# LM2903_CAT5171TBI.net
KiCad netlist of a schematic drawn in Altium Designer
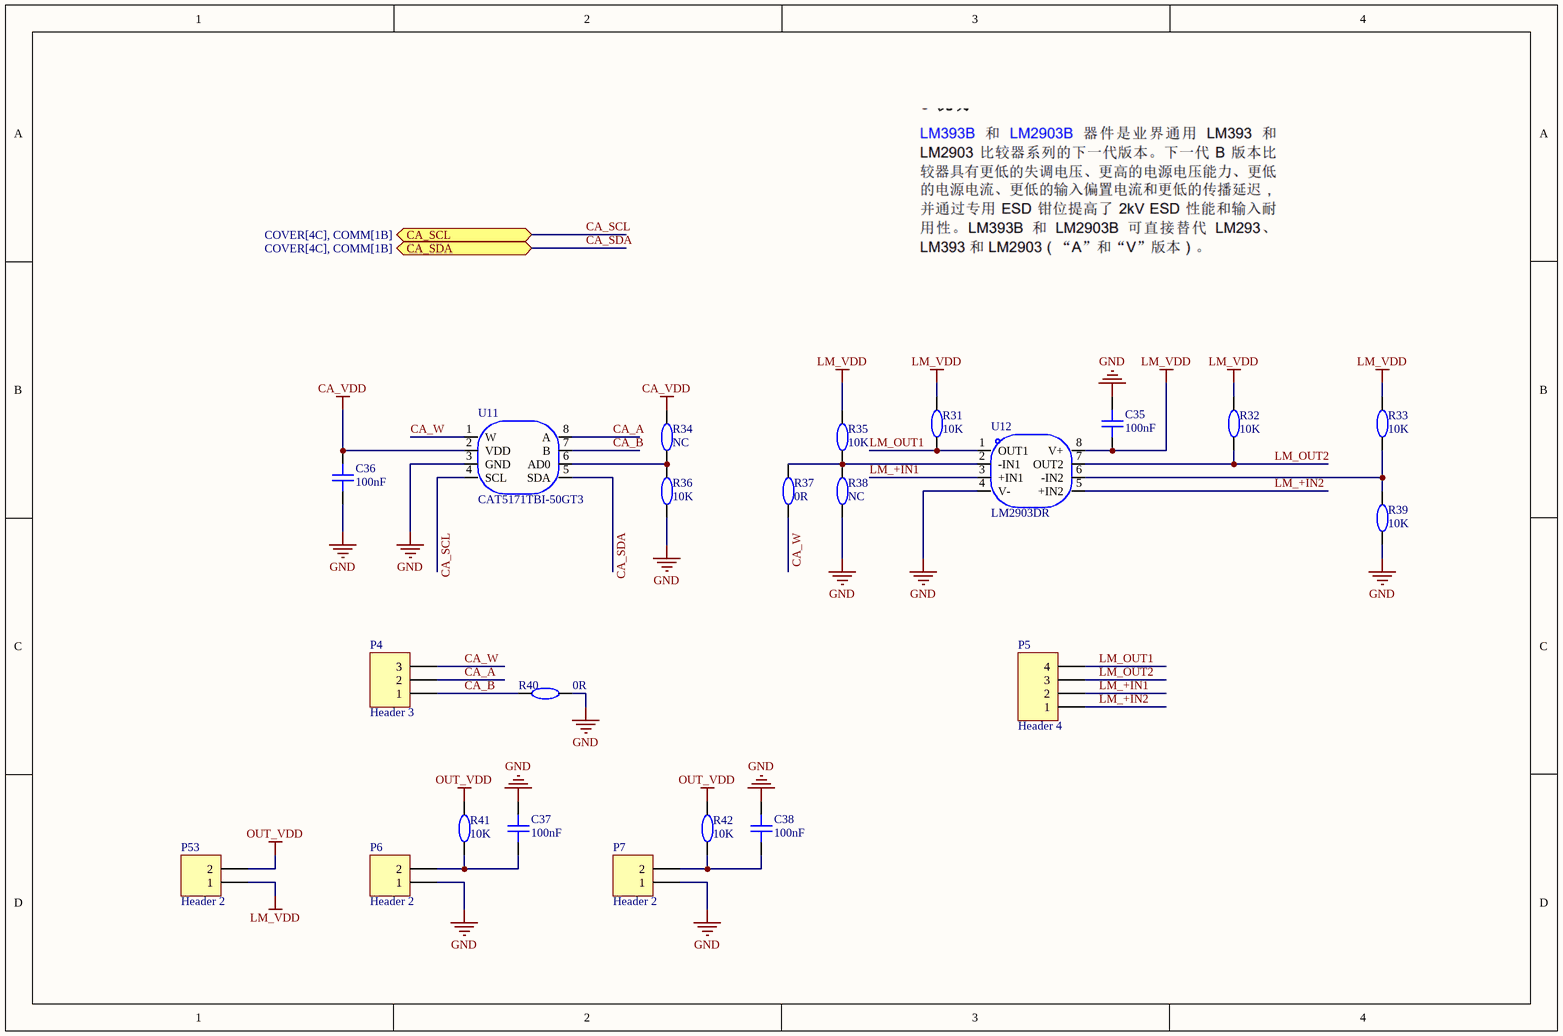
[diagram p0: LM2903+CAT5171TBI.SchDoc]

(export (version "E")
  (design (tool "Eeschema 10.0.6"))
  (components
    (comp (ref "C35")
      (value "100nF")
      (footprint "C0402")
      (fields (field (name "NAME") "100nF"))
      (libsource (lib "my_library") (part "CAP_0402"))
    )
    (comp (ref "C36")
      (value "100nF")
      (footprint "C0402")
      (fields (field (name "NAME") "100nF"))
      (libsource (lib "my_library") (part "CAP_0402"))
    )
    (comp (ref "C37")
      (value "100nF")
      (footprint "C0402")
      (fields (field (name "NAME") "100nF"))
      (libsource (lib "my_library") (part "CAP_0402"))
    )
    (comp (ref "C38")
      (value "100nF")
      (footprint "C0402")
      (fields (field (name "NAME") "100nF"))
      (libsource (lib "my_library") (part "CAP_0402"))
    )
    (comp (ref "P4")
      (value "Header 3")
      (footprint "HDR1X3")
      (description "Header, 3-Pin")
      (fields (field (name "PUBLISHER") "Altium Limited"))
      (libsource (lib "Miscellaneous Connectors") (part "Header 3"))
    )
    (comp (ref "P5")
      (value "Header 4")
      (footprint "HDR1X4")
      (description "Header, 4-Pin")
      (fields (field (name "PUBLISHER") "Altium Limited"))
      (libsource (lib "Miscellaneous Connectors") (part "Header 4"))
    )
    (comp (ref "P6")
      (value "Header 2")
      (footprint "HDR1X2")
      (description "Header, 2-Pin")
      (fields (field (name "PUBLISHER") "Altium Limited"))
      (libsource (lib "Miscellaneous Connectors") (part "Header 2"))
    )
    (comp (ref "P7")
      (value "Header 2")
      (footprint "HDR1X2")
      (description "Header, 2-Pin")
      (fields (field (name "PUBLISHER") "Altium Limited"))
      (libsource (lib "Miscellaneous Connectors") (part "Header 2"))
    )
    (comp (ref "P53")
      (value "Header 2")
      (footprint "HDR1X2")
      (description "Header, 2-Pin")
      (fields (field (name "PUBLISHER") "Altium Limited"))
      (libsource (lib "Miscellaneous Connectors") (part "Header 2"))
    )
    (comp (ref "R31")
      (value "10K")
      (footprint "R0402")
      (fields (field (name "NAME") "10K"))
      (libsource (lib "my_library") (part "Res_0402"))
    )
    (comp (ref "R32")
      (value "10K")
      (footprint "R0402")
      (fields (field (name "NAME") "10K"))
      (libsource (lib "my_library") (part "Res_0402"))
    )
    (comp (ref "R33")
      (value "10K")
      (footprint "R0603")
      (fields (field (name "NAME") "10K"))
      (libsource (lib "my_library") (part "Res_0603"))
    )
    (comp (ref "R34")
      (value "NC")
      (footprint "R0402")
      (fields (field (name "NAME") "NC"))
      (libsource (lib "my_library") (part "Res_0402"))
    )
    (comp (ref "R35")
      (value "10K")
      (footprint "R0603")
      (fields (field (name "NAME") "10K"))
      (libsource (lib "my_library") (part "Res_0603"))
    )
    (comp (ref "R36")
      (value "10K")
      (footprint "R0402")
      (fields (field (name "NAME") "10K"))
      (libsource (lib "my_library") (part "Res_0402"))
    )
    (comp (ref "R37")
      (value "0R")
      (footprint "R0603")
      (fields (field (name "NAME") "0R"))
      (libsource (lib "my_library") (part "Res_0603"))
    )
    (comp (ref "R38")
      (value "NC")
      (footprint "R0603")
      (fields (field (name "NAME") "NC"))
      (libsource (lib "my_library") (part "Res_0603"))
    )
    (comp (ref "R39")
      (value "10K")
      (footprint "R0603")
      (fields (field (name "NAME") "10K"))
      (libsource (lib "my_library") (part "Res_0603"))
    )
    (comp (ref "R40")
      (value "0R")
      (footprint "R0603")
      (fields (field (name "NAME") "0R"))
      (libsource (lib "my_library") (part "Res_0603"))
    )
    (comp (ref "R41")
      (value "10K")
      (footprint "R0402")
      (fields (field (name "NAME") "10K"))
      (libsource (lib "my_library") (part "Res_0402"))
    )
    (comp (ref "R42")
      (value "10K")
      (footprint "R0402")
      (fields (field (name "NAME") "10K"))
      (libsource (lib "my_library") (part "Res_0402"))
    )
    (comp (ref "U11")
      (value "CAT5171TBI-50GT3")
      (footprint "SOT-23-8_L3.0-W1.7-P0.65-LS2.8-BR")
      (fields
        (field (name "MANUFACTURER") "onsemi(安森美)")
        (field (name "TOLERANCE") "±20%")
        (field (name "NAME") "CAT5171TBI-50GT3")
      )
      (libsource (lib "my_library") (part "CAT5171TBI-50GT3"))
    )
    (comp (ref "U12")
      (value "LM2903DR")
      (footprint "SOIC-8_L5.0-W4.0-P1.27-LS6.0-BL")
      (fields (field (name "MANUFACTURER") "TI(德州仪器)") (field (name "NAME") "LM2903DR"))
      (libsource (lib "PCB_Project") (part "LM2903DR"))
    )
  )
  (nets
    (net (code "1") (name "/CA_A") (class "Default")
      (node (ref "P4") (pin "2") (pinfunction "2_2") (pintype "passive"))
      (node (ref "U11") (pin "8") (pinfunction "A_8") (pintype "passive"))
    )
    (net (code "2") (name "/CA_B") (class "Default")
      (node (ref "P4") (pin "1") (pinfunction "1_1") (pintype "passive"))
      (node (ref "R40") (pin "2") (pinfunction "2_2") (pintype "passive"))
      (node (ref "U11") (pin "7") (pinfunction "B_7") (pintype "passive"))
    )
    (net (code "3") (name "/CA_SCL") (class "Default")
      (node (ref "U11") (pin "4") (pinfunction "SCL_4") (pintype "passive"))
    )
    (net (code "4") (name "/CA_SDA") (class "Default")
      (node (ref "U11") (pin "5") (pinfunction "SDA_5") (pintype "passive"))
    )
    (net (code "5") (name "/CA_W") (class "Default")
      (node (ref "P4") (pin "3") (pinfunction "3_3") (pintype "passive"))
      (node (ref "R37") (pin "1") (pinfunction "1_1") (pintype "passive"))
      (node (ref "U11") (pin "1") (pinfunction "W_1") (pintype "passive"))
    )
    (net (code "6") (name "/LM_+IN1") (class "Default")
      (node (ref "P5") (pin "2") (pinfunction "2_2") (pintype "passive"))
      (node (ref "U12") (pin "3") (pinfunction "+IN1_3") (pintype "passive"))
    )
    (net (code "7") (name "/LM_+IN2") (class "Default")
      (node (ref "P5") (pin "1") (pinfunction "1_1") (pintype "passive"))
      (node (ref "U12") (pin "5") (pinfunction "+IN2_5") (pintype "passive"))
    )
    (net (code "8") (name "/LM_OUT1") (class "Default")
      (node (ref "P5") (pin "4") (pinfunction "4_4") (pintype "passive"))
      (node (ref "R31") (pin "1") (pinfunction "1_1") (pintype "passive"))
      (node (ref "U12") (pin "1") (pinfunction "OUT1_1") (pintype "passive"))
    )
    (net (code "9") (name "/LM_OUT2") (class "Default")
      (node (ref "P5") (pin "3") (pinfunction "3_3") (pintype "passive"))
      (node (ref "R32") (pin "1") (pinfunction "1_1") (pintype "passive"))
      (node (ref "U12") (pin "7") (pinfunction "OUT2_7") (pintype "passive"))
    )
    (net (code "10") (name "CA_VDD") (class "Default")
      (node (ref "C36") (pin "2") (pinfunction "2_2") (pintype "passive"))
      (node (ref "R34") (pin "2") (pinfunction "2_2") (pintype "passive"))
      (node (ref "U11") (pin "2") (pinfunction "VDD_2") (pintype "passive"))
    )
    (net (code "11") (name "GND") (class "Default")
      (node (ref "C35") (pin "2") (pinfunction "2_2") (pintype "passive"))
      (node (ref "C36") (pin "1") (pinfunction "1_1") (pintype "passive"))
      (node (ref "C37") (pin "2") (pinfunction "2_2") (pintype "passive"))
      (node (ref "C38") (pin "2") (pinfunction "2_2") (pintype "passive"))
      (node (ref "P6") (pin "1") (pinfunction "1_1") (pintype "passive"))
      (node (ref "P7") (pin "1") (pinfunction "1_1") (pintype "passive"))
      (node (ref "R36") (pin "1") (pinfunction "1_1") (pintype "passive"))
      (node (ref "R38") (pin "1") (pinfunction "1_1") (pintype "passive"))
      (node (ref "R39") (pin "1") (pinfunction "1_1") (pintype "passive"))
      (node (ref "R40") (pin "1") (pinfunction "1_1") (pintype "passive"))
      (node (ref "U11") (pin "3") (pinfunction "GND_3") (pintype "passive"))
      (node (ref "U12") (pin "4") (pinfunction "V-_4") (pintype "passive"))
    )
    (net (code "12") (name "LM_VDD") (class "Default")
      (node (ref "C35") (pin "1") (pinfunction "1_1") (pintype "passive"))
      (node (ref "P53") (pin "1") (pinfunction "1_1") (pintype "passive"))
      (node (ref "R31") (pin "2") (pinfunction "2_2") (pintype "passive"))
      (node (ref "R32") (pin "2") (pinfunction "2_2") (pintype "passive"))
      (node (ref "R33") (pin "2") (pinfunction "2_2") (pintype "passive"))
      (node (ref "R35") (pin "2") (pinfunction "2_2") (pintype "passive"))
      (node (ref "U12") (pin "8") (pinfunction "V+_8") (pintype "passive"))
    )
    (net (code "13") (name "Net-(C37-Pad1)") (class "Default")
      (node (ref "C37") (pin "1") (pinfunction "1_1") (pintype "passive"))
      (node (ref "P6") (pin "2") (pinfunction "2_2") (pintype "passive"))
      (node (ref "R41") (pin "1") (pinfunction "1_1") (pintype "passive"))
    )
    (net (code "14") (name "Net-(C38-Pad1)") (class "Default")
      (node (ref "C38") (pin "1") (pinfunction "1_1") (pintype "passive"))
      (node (ref "P7") (pin "2") (pinfunction "2_2") (pintype "passive"))
      (node (ref "R42") (pin "1") (pinfunction "1_1") (pintype "passive"))
    )
    (net (code "15") (name "Net-(U11-AD0)") (class "Default")
      (node (ref "R34") (pin "1") (pinfunction "1_1") (pintype "passive"))
      (node (ref "R36") (pin "2") (pinfunction "2_2") (pintype "passive"))
      (node (ref "U11") (pin "6") (pinfunction "AD0_6") (pintype "passive"))
    )
    (net (code "16") (name "Net-(U12--IN1)") (class "Default")
      (node (ref "R35") (pin "1") (pinfunction "1_1") (pintype "passive"))
      (node (ref "R37") (pin "2") (pinfunction "2_2") (pintype "passive"))
      (node (ref "R38") (pin "2") (pinfunction "2_2") (pintype "passive"))
      (node (ref "U12") (pin "2") (pinfunction "-IN1_2") (pintype "passive"))
    )
    (net (code "17") (name "Net-(U12--IN2)") (class "Default")
      (node (ref "R33") (pin "1") (pinfunction "1_1") (pintype "passive"))
      (node (ref "R39") (pin "2") (pinfunction "2_2") (pintype "passive"))
      (node (ref "U12") (pin "6") (pinfunction "-IN2_6") (pintype "passive"))
    )
    (net (code "18") (name "OUT_VDD") (class "Default")
      (node (ref "P53") (pin "2") (pinfunction "2_2") (pintype "passive"))
      (node (ref "R41") (pin "2") (pinfunction "2_2") (pintype "passive"))
      (node (ref "R42") (pin "2") (pinfunction "2_2") (pintype "passive"))
    )
  )
)
